# MCU-Debug.net
KiCad netlist of a schematic drawn in Altium Designer
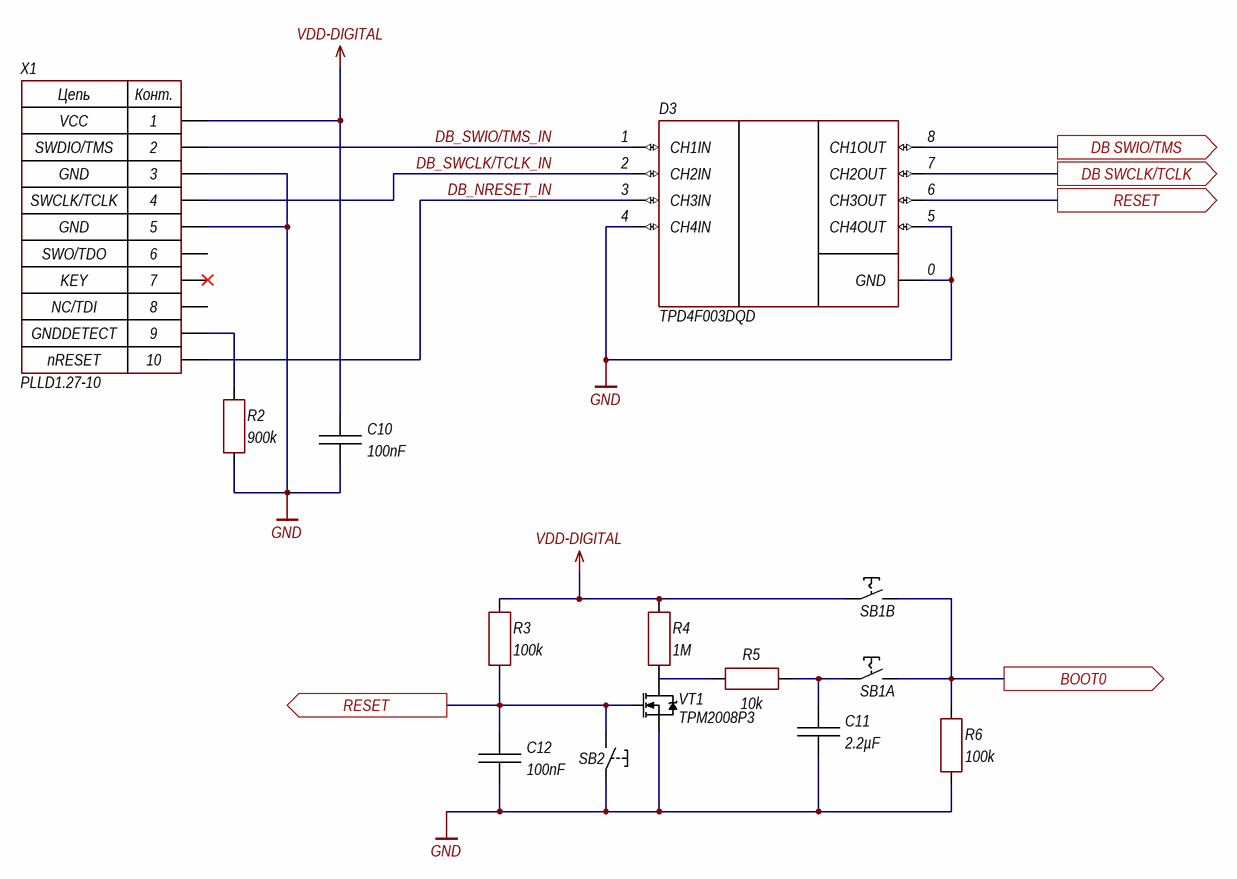
[diagram p0: MCU-Debug.SchDoc]

(export (version "E")
  (design (tool "Eeschema 10.0.6"))
  (components
    (comp (ref "C10") (value "100nF") (footprint "CH0402C") (libsource (lib "Discrete") (part "Capacitor")))
    (comp (ref "C11") (value "2.2µF") (footprint "CH0402C") (libsource (lib "Discrete") (part "Capacitor")))
    (comp (ref "C12") (value "100nF") (footprint "CH0402C") (libsource (lib "Discrete") (part "Capacitor")))
    (comp (ref "D3")
      (value "TPD4F003DQD")
      (footprint "8-WSON (1.7x1.35 mm)")
      (description "4-bit IO protection")
      (fields (field (name "MANUFACTURER") "Texas Instruments"))
      (libsource (lib "Analog") (part "TPD4F003"))
    )
    (comp (ref "R2") (value "900k") (footprint "CH0402R") (libsource (lib "") (part "Resistor_1")))
    (comp (ref "R3") (value "100k") (footprint "CH0402R") (libsource (lib "") (part "Resistor_1")))
    (comp (ref "R4") (value "1M") (footprint "CH0402R") (libsource (lib "") (part "Resistor_1")))
    (comp (ref "R5") (value "10k") (footprint "CH0402R") (libsource (lib "Discrete") (part "Resistor")))
    (comp (ref "R6") (value "100k") (footprint "CH0402R") (libsource (lib "") (part "Resistor_1")))
    (comp (ref "SB1")
      (value "*")
      (footprint "BUT: DSHP02TS")
      (description "2 Array, latching")
      (libsource (lib "Connectors") (part "2(1)-Switch"))
    )
    (comp (ref "SB2")
      (value "\"Кнопка\"")
      (footprint "BUT: YTS-A017")
      (description "Button, no latching")
      (libsource (lib "Connectors") (part "1-Button"))
    )
    (comp (ref "VT1")
      (value "TPM2008P3")
      (footprint "DFN1006-3L")
      (description "Mosfet")
      (fields (field (name "MANUFACTURER") "TECH PUBLIC"))
      (libsource (lib "Transistor") (part "N-chanel"))
    )
    (comp (ref "X1")
      (value "PLLD1.27-10")
      (footprint "CON: PLLD-1.27-10")
      (libsource (lib "Connectors") (part "10-Connector"))
    )
  )
  (nets
    (net (code "1") (name "/BOOT0") (class "Default")
      (node (ref "R6") (pin "2") (pinfunction "2_2") (pintype "passive"))
      (node (ref "SB1") (pin "3") (pinfunction "3_3") (pintype "passive"))
      (node (ref "SB1") (pin "4") (pinfunction "4_4") (pintype "passive"))
    )
    (net (code "2") (name "/DB SWCLK{slash}TCLK") (class "Default")
      (node (ref "D3") (pin "7") (pinfunction "CH2OUT_7") (pintype "bidirectional"))
    )
    (net (code "3") (name "/DB SWIO{slash}TMS") (class "Default")
      (node (ref "D3") (pin "8") (pinfunction "CH1OUT_8") (pintype "bidirectional"))
    )
    (net (code "4") (name "/DB_NRESET_IN") (class "Default")
      (node (ref "D3") (pin "3") (pinfunction "CH3IN_3") (pintype "bidirectional"))
      (node (ref "X1") (pin "10") (pinfunction "10_10") (pintype "passive"))
    )
    (net (code "5") (name "/DB_SWCLK{slash}TCLK_IN") (class "Default")
      (node (ref "D3") (pin "2") (pinfunction "CH2IN_2") (pintype "bidirectional"))
      (node (ref "X1") (pin "4") (pinfunction "4_4") (pintype "passive"))
    )
    (net (code "6") (name "/DB_SWIO{slash}TMS_IN") (class "Default")
      (node (ref "D3") (pin "1") (pinfunction "CH1IN_1") (pintype "bidirectional"))
      (node (ref "X1") (pin "2") (pinfunction "2_2") (pintype "passive"))
    )
    (net (code "7") (name "/RESET") (class "Default")
      (node (ref "C12") (pin "2") (pinfunction "2_2") (pintype "passive"))
      (node (ref "D3") (pin "6") (pinfunction "CH3OUT_6") (pintype "bidirectional"))
      (node (ref "R3") (pin "1") (pinfunction "1_1") (pintype "passive"))
      (node (ref "SB2") (pin "2") (pinfunction "2_2") (pintype "passive"))
      (node (ref "VT1") (pin "1") (pinfunction "G_1") (pintype "passive"))
    )
    (net (code "8") (name "GND") (class "Default")
      (node (ref "C10") (pin "1") (pinfunction "1_1") (pintype "passive"))
      (node (ref "C11") (pin "1") (pinfunction "1_1") (pintype "passive"))
      (node (ref "C12") (pin "1") (pinfunction "1_1") (pintype "passive"))
      (node (ref "D3") (pin "0") (pinfunction "GND_0") (pintype "power_in"))
      (node (ref "D3") (pin "4") (pinfunction "CH4IN_4") (pintype "bidirectional"))
      (node (ref "D3") (pin "5") (pinfunction "CH4OUT_5") (pintype "bidirectional"))
      (node (ref "R2") (pin "1") (pinfunction "1_1") (pintype "passive"))
      (node (ref "R6") (pin "1") (pinfunction "1_1") (pintype "passive"))
      (node (ref "SB2") (pin "1") (pinfunction "1_1") (pintype "passive"))
      (node (ref "VT1") (pin "3") (pinfunction "S_3") (pintype "passive"))
      (node (ref "X1") (pin "3") (pinfunction "3_3") (pintype "passive"))
      (node (ref "X1") (pin "5") (pinfunction "5_5") (pintype "passive"))
    )
    (net (code "9") (name "Net-(C11-Pad2)") (class "Default")
      (node (ref "C11") (pin "2") (pinfunction "2_2") (pintype "passive"))
      (node (ref "R5") (pin "2") (pinfunction "2_2") (pintype "passive"))
      (node (ref "SB1") (pin "1") (pinfunction "1_1") (pintype "passive"))
    )
    (net (code "10") (name "Net-(R2-Pad2)") (class "Default")
      (node (ref "R2") (pin "2") (pinfunction "2_2") (pintype "passive"))
      (node (ref "X1") (pin "9") (pinfunction "9_9") (pintype "passive"))
    )
    (net (code "11") (name "Net-(VT1-D)") (class "Default")
      (node (ref "R4") (pin "1") (pinfunction "1_1") (pintype "passive"))
      (node (ref "R5") (pin "1") (pinfunction "1_1") (pintype "passive"))
      (node (ref "VT1") (pin "2") (pinfunction "D_2") (pintype "passive"))
    )
    (net (code "12") (name "VDD-DIGITAL") (class "Default")
      (node (ref "C10") (pin "2") (pinfunction "2_2") (pintype "passive"))
      (node (ref "R3") (pin "2") (pinfunction "2_2") (pintype "passive"))
      (node (ref "R4") (pin "2") (pinfunction "2_2") (pintype "passive"))
      (node (ref "SB1") (pin "2") (pinfunction "2_2") (pintype "passive"))
      (node (ref "X1") (pin "1") (pinfunction "1_1") (pintype "passive"))
    )
    (net (code "13") (name "unconnected-(X1-Pad6)") (class "Default")
      (node (ref "X1") (pin "6") (pinfunction "6_6") (pintype "passive"))
    )
    (net (code "14") (name "unconnected-(X1-Pad7)") (class "Default")
      (node (ref "X1") (pin "7") (pinfunction "7_7") (pintype "passive+no_connect"))
    )
    (net (code "15") (name "unconnected-(X1-Pad8)") (class "Default")
      (node (ref "X1") (pin "8") (pinfunction "8_8") (pintype "passive"))
    )
  )
)
